# Evaluation_Board.net
KiCad netlist of a schematic drawn in EAGLE
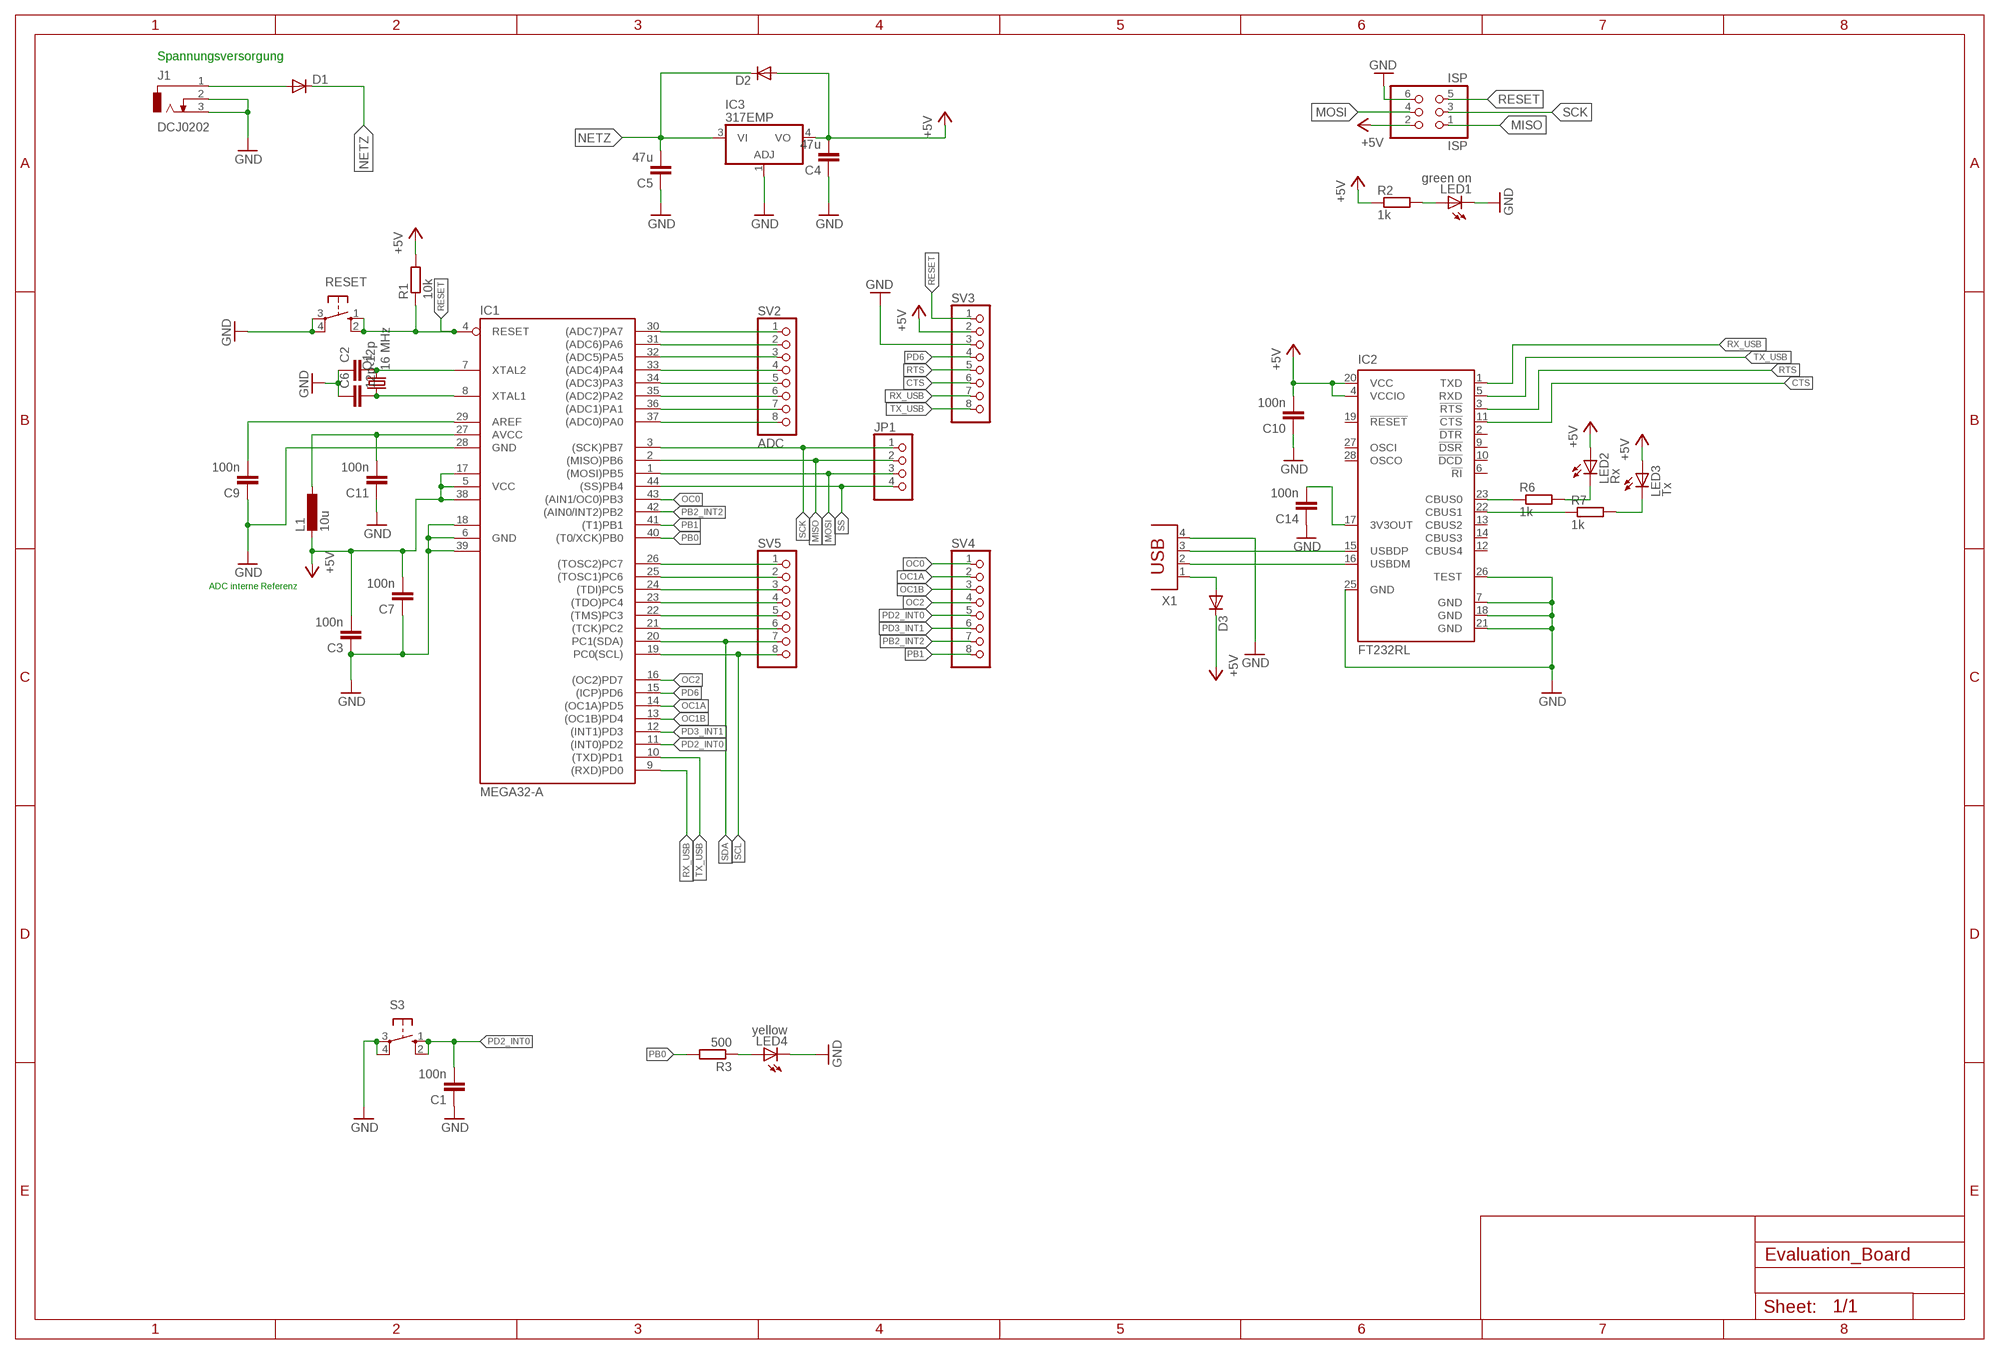
[diagram p0: schematic, sheet 1]

(export (version "E")
  (design (tool "Eeschema 10.0.6"))
  (components
    (comp (ref "C1")
      (value "100n")
      (footprint "eagle-import:C0805")
      (libsource (lib "eagle-import") (part "C-EUC0805"))
    )
    (comp (ref "C2")
      (value "12p")
      (footprint "eagle-import:C0805")
      (libsource (lib "eagle-import") (part "C-EUC0805"))
    )
    (comp (ref "C3")
      (value "100n")
      (footprint "eagle-import:C0805")
      (libsource (lib "eagle-import") (part "C-EUC0805"))
    )
    (comp (ref "C4")
      (value "47u")
      (footprint "eagle-import:C0805")
      (libsource (lib "eagle-import") (part "C-EUC0805"))
    )
    (comp (ref "C5")
      (value "47u")
      (footprint "eagle-import:C0805")
      (libsource (lib "eagle-import") (part "C-EUC0805"))
    )
    (comp (ref "C6")
      (value "12p")
      (footprint "eagle-import:C0805")
      (libsource (lib "eagle-import") (part "C-EUC0805"))
    )
    (comp (ref "C7")
      (value "100n")
      (footprint "eagle-import:C0805")
      (libsource (lib "eagle-import") (part "C-EUC0805"))
    )
    (comp (ref "C9")
      (value "100n")
      (footprint "eagle-import:C0805")
      (libsource (lib "eagle-import") (part "C-EUC0805"))
    )
    (comp (ref "C10")
      (value "100n")
      (footprint "eagle-import:C0805")
      (libsource (lib "eagle-import") (part "C-EUC0805"))
    )
    (comp (ref "C11")
      (value "100n")
      (footprint "eagle-import:C0805")
      (libsource (lib "eagle-import") (part "C-EUC0805"))
    )
    (comp (ref "C14")
      (value "100n")
      (footprint "eagle-import:C0805")
      (libsource (lib "eagle-import") (part "C-EUC0805"))
    )
    (comp (ref "D1")
      (value "DIODE-MINIMELF")
      (footprint "eagle-import:MINIMELF")
      (libsource (lib "eagle-import") (part "DIODE-MINIMELF"))
    )
    (comp (ref "D2")
      (value "DIODE-MINIMELF")
      (footprint "eagle-import:MINIMELF")
      (libsource (lib "eagle-import") (part "DIODE-MINIMELF"))
    )
    (comp (ref "D3")
      (value "DIODE-MINIMELF")
      (footprint "eagle-import:MINIMELF")
      (libsource (lib "eagle-import") (part "DIODE-MINIMELF"))
    )
    (comp (ref "IC1")
      (value "MEGA32-A")
      (footprint "eagle-import:TQFP44")
      (fields (field (name "MPN") "ATMEGA32-16AU"))
      (libsource (lib "eagle-import") (part "MEGA32-A"))
    )
    (comp (ref "IC2")
      (value "FT232RL")
      (footprint "eagle-import:SSOP28")
      (libsource (lib "eagle-import") (part "FT232RL"))
    )
    (comp (ref "IC3")
      (value "317EMP")
      (footprint "eagle-import:SOT223")
      (libsource (lib "eagle-import") (part "317EMP"))
    )
    (comp (ref "ISP")
      (value "ISP")
      (footprint "eagle-import:2X03")
      (libsource (lib "eagle-import") (part "PINHD-2X3"))
    )
    (comp (ref "J1")
      (value "DCJ0202")
      (footprint "eagle-import:DCJ0202")
      (libsource (lib "eagle-import") (part "DCJ0202"))
    )
    (comp (ref "JP1")
      (value "PINHD-1X4")
      (footprint "eagle-import:1X04")
      (libsource (lib "eagle-import") (part "PINHD-1X4"))
    )
    (comp (ref "L1")
      (value "10u")
      (footprint "eagle-import:L3225M")
      (libsource (lib "eagle-import") (part "L-EUL3225M"))
    )
    (comp (ref "LED1")
      (value "green on")
      (footprint "eagle-import:SML0805")
      (libsource (lib "eagle-import") (part "LEDSML0805"))
    )
    (comp (ref "LED2")
      (value "Rx")
      (footprint "eagle-import:SML0805")
      (libsource (lib "eagle-import") (part "LEDSML0805"))
    )
    (comp (ref "LED3")
      (value "Tx")
      (footprint "eagle-import:SML0805")
      (libsource (lib "eagle-import") (part "LEDSML0805"))
    )
    (comp (ref "LED4")
      (value "yellow")
      (footprint "eagle-import:SML0805")
      (libsource (lib "eagle-import") (part "LEDSML0805"))
    )
    (comp (ref "Q1")
      (value "16 MHz")
      (footprint "eagle-import:HC49UP")
      (libsource (lib "eagle-import") (part "CRYSTALHC49UP"))
    )
    (comp (ref "R1")
      (value "10k")
      (footprint "eagle-import:R0805")
      (libsource (lib "eagle-import") (part "R-EU_R0805"))
    )
    (comp (ref "R2")
      (value "1k")
      (footprint "eagle-import:R0805")
      (libsource (lib "eagle-import") (part "R-EU_R0805"))
    )
    (comp (ref "R3")
      (value "500")
      (footprint "eagle-import:R0805")
      (libsource (lib "eagle-import") (part "R-EU_R0805"))
    )
    (comp (ref "R6")
      (value "1k")
      (footprint "eagle-import:R0805")
      (libsource (lib "eagle-import") (part "R-EU_R0805"))
    )
    (comp (ref "R7")
      (value "1k")
      (footprint "eagle-import:R0805")
      (libsource (lib "eagle-import") (part "R-EU_R0805"))
    )
    (comp (ref "RESET")
      (value "10-XX")
      (footprint "eagle-import:B3F-10XX")
      (fields (field (name "MPN") "B3F-1000"))
      (libsource (lib "eagle-import") (part "10-XX"))
    )
    (comp (ref "S3")
      (value "10-XX")
      (footprint "eagle-import:B3F-10XX")
      (fields (field (name "MPN") "B3F-1000"))
      (libsource (lib "eagle-import") (part "10-XX"))
    )
    (comp (ref "SV2")
      (value "ADC")
      (footprint "eagle-import:1X08")
      (libsource (lib "eagle-import") (part "PINHD-1X8"))
    )
    (comp (ref "SV3")
      (value "PINHD-1X8")
      (footprint "eagle-import:1X08")
      (libsource (lib "eagle-import") (part "PINHD-1X8"))
    )
    (comp (ref "SV4")
      (value "PINHD-1X8")
      (footprint "eagle-import:1X08")
      (libsource (lib "eagle-import") (part "PINHD-1X8"))
    )
    (comp (ref "SV5")
      (value "PINHD-1X8")
      (footprint "eagle-import:1X08")
      (libsource (lib "eagle-import") (part "PINHD-1X8"))
    )
    (comp (ref "X1")
      (value "USB-B-BUCHSE-HORIZONTAL")
      (footprint "eagle-import:USB-B-BUCHSE-HORIZONTAL")
      (libsource (lib "eagle-import") (part "USB-B-BUCHSE-HORIZONTAL"))
    )
  )
  (nets
    (net (code "1") (name "+5V") (class "Default")
      (node (ref "C10") (pin "2") (pinfunction "2_2") (pintype "passive"))
      (node (ref "C3") (pin "2") (pinfunction "2_2") (pintype "passive"))
      (node (ref "C4") (pin "2") (pinfunction "2_2") (pintype "passive"))
      (node (ref "C7") (pin "2") (pinfunction "2_2") (pintype "passive"))
      (node (ref "D2") (pin "A") (pinfunction "A_A") (pintype "passive"))
      (node (ref "D3") (pin "C") (pinfunction "C_C") (pintype "passive"))
      (node (ref "IC1") (pin "17") (pinfunction "VCC1_17") (pintype "power_in"))
      (node (ref "IC1") (pin "38") (pinfunction "VCC2_38") (pintype "power_in"))
      (node (ref "IC1") (pin "5") (pinfunction "VCC_5") (pintype "power_in"))
      (node (ref "IC2") (pin "20") (pinfunction "VCC_20") (pintype "power_in"))
      (node (ref "IC2") (pin "4") (pinfunction "VCCIO_4") (pintype "power_in"))
      (node (ref "IC3") (pin "4") (pinfunction "VO_4") (pintype "passive"))
      (node (ref "ISP") (pin "2") (pinfunction "2_2") (pintype "passive"))
      (node (ref "L1") (pin "2") (pinfunction "2_2") (pintype "passive"))
      (node (ref "LED2") (pin "A") (pinfunction "A_A") (pintype "passive"))
      (node (ref "LED3") (pin "A") (pinfunction "A_A") (pintype "passive"))
      (node (ref "R1") (pin "2") (pinfunction "2_2") (pintype "passive"))
      (node (ref "R2") (pin "1") (pinfunction "1_1") (pintype "passive"))
      (node (ref "SV3") (pin "2") (pinfunction "2_2") (pintype "passive"))
    )
    (net (code "2") (name "CTS") (class "Default")
      (node (ref "IC2") (pin "11") (pinfunction "~{CTS}_11") (pintype "input"))
      (node (ref "SV3") (pin "6") (pinfunction "6_6") (pintype "passive"))
    )
    (net (code "3") (name "GND") (class "Default")
      (node (ref "C1") (pin "1") (pinfunction "1_1") (pintype "passive"))
      (node (ref "C10") (pin "1") (pinfunction "1_1") (pintype "passive"))
      (node (ref "C11") (pin "1") (pinfunction "1_1") (pintype "passive"))
      (node (ref "C14") (pin "1") (pinfunction "1_1") (pintype "passive"))
      (node (ref "C2") (pin "1") (pinfunction "1_1") (pintype "passive"))
      (node (ref "C3") (pin "1") (pinfunction "1_1") (pintype "passive"))
      (node (ref "C4") (pin "1") (pinfunction "1_1") (pintype "passive"))
      (node (ref "C5") (pin "1") (pinfunction "1_1") (pintype "passive"))
      (node (ref "C6") (pin "1") (pinfunction "1_1") (pintype "passive"))
      (node (ref "C7") (pin "1") (pinfunction "1_1") (pintype "passive"))
      (node (ref "C9") (pin "1") (pinfunction "1_1") (pintype "passive"))
      (node (ref "IC1") (pin "18") (pinfunction "GND1_18") (pintype "power_in"))
      (node (ref "IC1") (pin "28") (pinfunction "GND_28") (pintype "power_in"))
      (node (ref "IC1") (pin "39") (pinfunction "GND2_39") (pintype "power_in"))
      (node (ref "IC1") (pin "6") (pinfunction "GND_6") (pintype "power_in"))
      (node (ref "IC2") (pin "18") (pinfunction "GND_18") (pintype "power_in"))
      (node (ref "IC2") (pin "21") (pinfunction "GND_21") (pintype "power_in"))
      (node (ref "IC2") (pin "25") (pinfunction "GND_25") (pintype "power_in"))
      (node (ref "IC2") (pin "26") (pinfunction "TEST_26") (pintype "input"))
      (node (ref "IC2") (pin "7") (pinfunction "GND_7") (pintype "power_in"))
      (node (ref "IC3") (pin "1") (pinfunction "ADJ_1") (pintype "input"))
      (node (ref "ISP") (pin "6") (pinfunction "6_6") (pintype "passive"))
      (node (ref "J1") (pin "2") (pinfunction "2_2") (pintype "passive"))
      (node (ref "J1") (pin "3") (pinfunction "3_3") (pintype "passive"))
      (node (ref "LED1") (pin "C") (pinfunction "C_C") (pintype "passive"))
      (node (ref "LED4") (pin "C") (pinfunction "C_C") (pintype "passive"))
      (node (ref "RESET") (pin "3") (pinfunction "P_3") (pintype "passive"))
      (node (ref "RESET") (pin "4") (pinfunction "P1_4") (pintype "passive"))
      (node (ref "S3") (pin "3") (pinfunction "P_3") (pintype "passive"))
      (node (ref "S3") (pin "4") (pinfunction "P1_4") (pintype "passive"))
      (node (ref "SV3") (pin "3") (pinfunction "3_3") (pintype "passive"))
      (node (ref "X1") (pin "4") (pinfunction "4_4") (pintype "passive"))
    )
    (net (code "4") (name "MISO") (class "Default")
      (node (ref "IC1") (pin "2") (pinfunction "(MISO)PB6_2") (pintype "bidirectional"))
      (node (ref "ISP") (pin "1") (pinfunction "1_1") (pintype "passive"))
      (node (ref "JP1") (pin "2") (pinfunction "2_2") (pintype "passive"))
    )
    (net (code "5") (name "MOSI") (class "Default")
      (node (ref "IC1") (pin "1") (pinfunction "(MOSI)PB5_1") (pintype "bidirectional"))
      (node (ref "ISP") (pin "4") (pinfunction "4_4") (pintype "passive"))
      (node (ref "JP1") (pin "3") (pinfunction "3_3") (pintype "passive"))
    )
    (net (code "6") (name "NETZ") (class "Default")
      (node (ref "C5") (pin "2") (pinfunction "2_2") (pintype "passive"))
      (node (ref "D1") (pin "C") (pinfunction "C_C") (pintype "passive"))
      (node (ref "D2") (pin "C") (pinfunction "C_C") (pintype "passive"))
      (node (ref "IC3") (pin "3") (pinfunction "VI_3") (pintype "input"))
    )
    (net (code "7") (name "Net-(D1-PadA)") (class "Default")
      (node (ref "D1") (pin "A") (pinfunction "A_A") (pintype "passive"))
      (node (ref "J1") (pin "1") (pinfunction "1_1") (pintype "passive"))
    )
    (net (code "8") (name "Net-(D3-PadA)") (class "Default")
      (node (ref "D3") (pin "A") (pinfunction "A_A") (pintype "passive"))
      (node (ref "X1") (pin "1") (pinfunction "1_1") (pintype "passive"))
    )
    (net (code "9") (name "Net-(IC1-(ADC0)PA0)") (class "Default")
      (node (ref "IC1") (pin "37") (pinfunction "(ADC0)PA0_37") (pintype "bidirectional"))
      (node (ref "SV2") (pin "8") (pinfunction "8_8") (pintype "passive"))
    )
    (net (code "10") (name "Net-(IC1-(ADC1)PA1)") (class "Default")
      (node (ref "IC1") (pin "36") (pinfunction "(ADC1)PA1_36") (pintype "bidirectional"))
      (node (ref "SV2") (pin "7") (pinfunction "7_7") (pintype "passive"))
    )
    (net (code "11") (name "Net-(IC1-(ADC2)PA2)") (class "Default")
      (node (ref "IC1") (pin "35") (pinfunction "(ADC2)PA2_35") (pintype "bidirectional"))
      (node (ref "SV2") (pin "6") (pinfunction "6_6") (pintype "passive"))
    )
    (net (code "12") (name "Net-(IC1-(ADC3)PA3)") (class "Default")
      (node (ref "IC1") (pin "34") (pinfunction "(ADC3)PA3_34") (pintype "bidirectional"))
      (node (ref "SV2") (pin "5") (pinfunction "5_5") (pintype "passive"))
    )
    (net (code "13") (name "Net-(IC1-(ADC4)PA4)") (class "Default")
      (node (ref "IC1") (pin "33") (pinfunction "(ADC4)PA4_33") (pintype "bidirectional"))
      (node (ref "SV2") (pin "4") (pinfunction "4_4") (pintype "passive"))
    )
    (net (code "14") (name "Net-(IC1-(ADC5)PA5)") (class "Default")
      (node (ref "IC1") (pin "32") (pinfunction "(ADC5)PA5_32") (pintype "bidirectional"))
      (node (ref "SV2") (pin "3") (pinfunction "3_3") (pintype "passive"))
    )
    (net (code "15") (name "Net-(IC1-(ADC6)PA6)") (class "Default")
      (node (ref "IC1") (pin "31") (pinfunction "(ADC6)PA6_31") (pintype "bidirectional"))
      (node (ref "SV2") (pin "2") (pinfunction "2_2") (pintype "passive"))
    )
    (net (code "16") (name "Net-(IC1-(ADC7)PA7)") (class "Default")
      (node (ref "IC1") (pin "30") (pinfunction "(ADC7)PA7_30") (pintype "bidirectional"))
      (node (ref "SV2") (pin "1") (pinfunction "1_1") (pintype "passive"))
    )
    (net (code "17") (name "Net-(IC1-(TCK)PC2)") (class "Default")
      (node (ref "IC1") (pin "21") (pinfunction "(TCK)PC2_21") (pintype "bidirectional"))
      (node (ref "SV5") (pin "6") (pinfunction "6_6") (pintype "passive"))
    )
    (net (code "18") (name "Net-(IC1-(TDI)PC5)") (class "Default")
      (node (ref "IC1") (pin "24") (pinfunction "(TDI)PC5_24") (pintype "bidirectional"))
      (node (ref "SV5") (pin "3") (pinfunction "3_3") (pintype "passive"))
    )
    (net (code "19") (name "Net-(IC1-(TDO)PC4)") (class "Default")
      (node (ref "IC1") (pin "23") (pinfunction "(TDO)PC4_23") (pintype "bidirectional"))
      (node (ref "SV5") (pin "4") (pinfunction "4_4") (pintype "passive"))
    )
    (net (code "20") (name "Net-(IC1-(TMS)PC3)") (class "Default")
      (node (ref "IC1") (pin "22") (pinfunction "(TMS)PC3_22") (pintype "bidirectional"))
      (node (ref "SV5") (pin "5") (pinfunction "5_5") (pintype "passive"))
    )
    (net (code "21") (name "Net-(IC1-(TOSC1)PC6)") (class "Default")
      (node (ref "IC1") (pin "25") (pinfunction "(TOSC1)PC6_25") (pintype "bidirectional"))
      (node (ref "SV5") (pin "2") (pinfunction "2_2") (pintype "passive"))
    )
    (net (code "22") (name "Net-(IC1-(TOSC2)PC7)") (class "Default")
      (node (ref "IC1") (pin "26") (pinfunction "(TOSC2)PC7_26") (pintype "bidirectional"))
      (node (ref "SV5") (pin "1") (pinfunction "1_1") (pintype "passive"))
    )
    (net (code "23") (name "Net-(IC1-AREF)") (class "Default")
      (node (ref "C9") (pin "2") (pinfunction "2_2") (pintype "passive"))
      (node (ref "IC1") (pin "29") (pinfunction "AREF_29") (pintype "passive"))
    )
    (net (code "24") (name "Net-(IC1-AVCC)") (class "Default")
      (node (ref "C11") (pin "2") (pinfunction "2_2") (pintype "passive"))
      (node (ref "IC1") (pin "27") (pinfunction "AVCC_27") (pintype "power_in"))
      (node (ref "L1") (pin "1") (pinfunction "1_1") (pintype "passive"))
    )
    (net (code "25") (name "Net-(IC1-XTAL1)") (class "Default")
      (node (ref "C6") (pin "2") (pinfunction "2_2") (pintype "passive"))
      (node (ref "IC1") (pin "8") (pinfunction "XTAL1_8") (pintype "bidirectional"))
      (node (ref "Q1") (pin "1") (pinfunction "1_1") (pintype "passive"))
    )
    (net (code "26") (name "Net-(IC1-XTAL2)") (class "Default")
      (node (ref "C2") (pin "2") (pinfunction "2_2") (pintype "passive"))
      (node (ref "IC1") (pin "7") (pinfunction "XTAL2_7") (pintype "bidirectional"))
      (node (ref "Q1") (pin "2") (pinfunction "2_2") (pintype "passive"))
    )
    (net (code "27") (name "Net-(IC2-3V3OUT)") (class "Default")
      (node (ref "C14") (pin "2") (pinfunction "2_2") (pintype "passive"))
      (node (ref "IC2") (pin "17") (pinfunction "3V3OUT_17") (pintype "output"))
    )
    (net (code "28") (name "Net-(IC2-CBUS0)") (class "Default")
      (node (ref "IC2") (pin "23") (pinfunction "CBUS0_23") (pintype "bidirectional"))
      (node (ref "R6") (pin "1") (pinfunction "1_1") (pintype "passive"))
    )
    (net (code "29") (name "Net-(IC2-CBUS1)") (class "Default")
      (node (ref "IC2") (pin "22") (pinfunction "CBUS1_22") (pintype "bidirectional"))
      (node (ref "R7") (pin "1") (pinfunction "1_1") (pintype "passive"))
    )
    (net (code "30") (name "Net-(IC2-USBDM)") (class "Default")
      (node (ref "IC2") (pin "16") (pinfunction "USBDM_16") (pintype "bidirectional"))
      (node (ref "X1") (pin "2") (pinfunction "2_2") (pintype "passive"))
    )
    (net (code "31") (name "Net-(IC2-USBDP)") (class "Default")
      (node (ref "IC2") (pin "15") (pinfunction "USBDP_15") (pintype "bidirectional"))
      (node (ref "X1") (pin "3") (pinfunction "3_3") (pintype "passive"))
    )
    (net (code "32") (name "Net-(LED1-PadA)") (class "Default")
      (node (ref "LED1") (pin "A") (pinfunction "A_A") (pintype "passive"))
      (node (ref "R2") (pin "2") (pinfunction "2_2") (pintype "passive"))
    )
    (net (code "33") (name "Net-(LED2-PadC)") (class "Default")
      (node (ref "LED2") (pin "C") (pinfunction "C_C") (pintype "passive"))
      (node (ref "R6") (pin "2") (pinfunction "2_2") (pintype "passive"))
    )
    (net (code "34") (name "Net-(LED3-PadC)") (class "Default")
      (node (ref "LED3") (pin "C") (pinfunction "C_C") (pintype "passive"))
      (node (ref "R7") (pin "2") (pinfunction "2_2") (pintype "passive"))
    )
    (net (code "35") (name "Net-(LED4-PadA)") (class "Default")
      (node (ref "LED4") (pin "A") (pinfunction "A_A") (pintype "passive"))
      (node (ref "R3") (pin "1") (pinfunction "1_1") (pintype "passive"))
    )
    (net (code "36") (name "OC0") (class "Default")
      (node (ref "IC1") (pin "43") (pinfunction "(AIN1/OC0)PB3_43") (pintype "bidirectional"))
      (node (ref "SV4") (pin "1") (pinfunction "1_1") (pintype "passive"))
    )
    (net (code "37") (name "OC1A") (class "Default")
      (node (ref "IC1") (pin "14") (pinfunction "(OC1A)PD5_14") (pintype "bidirectional"))
      (node (ref "SV4") (pin "2") (pinfunction "2_2") (pintype "passive"))
    )
    (net (code "38") (name "OC1B") (class "Default")
      (node (ref "IC1") (pin "13") (pinfunction "(OC1B)PD4_13") (pintype "bidirectional"))
      (node (ref "SV4") (pin "3") (pinfunction "3_3") (pintype "passive"))
    )
    (net (code "39") (name "OC2") (class "Default")
      (node (ref "IC1") (pin "16") (pinfunction "(OC2)PD7_16") (pintype "bidirectional"))
      (node (ref "SV4") (pin "4") (pinfunction "4_4") (pintype "passive"))
    )
    (net (code "40") (name "PB0") (class "Default")
      (node (ref "IC1") (pin "40") (pinfunction "(T0/XCK)PB0_40") (pintype "bidirectional"))
      (node (ref "R3") (pin "2") (pinfunction "2_2") (pintype "passive"))
    )
    (net (code "41") (name "PB1") (class "Default")
      (node (ref "IC1") (pin "41") (pinfunction "(T1)PB1_41") (pintype "bidirectional"))
      (node (ref "SV4") (pin "8") (pinfunction "8_8") (pintype "passive"))
    )
    (net (code "42") (name "PB2_INT2") (class "Default")
      (node (ref "IC1") (pin "42") (pinfunction "(AIN0/INT2)PB2_42") (pintype "bidirectional"))
      (node (ref "SV4") (pin "7") (pinfunction "7_7") (pintype "passive"))
    )
    (net (code "43") (name "PD2_INT0") (class "Default")
      (node (ref "C1") (pin "2") (pinfunction "2_2") (pintype "passive"))
      (node (ref "IC1") (pin "11") (pinfunction "(INT0)PD2_11") (pintype "bidirectional"))
      (node (ref "S3") (pin "1") (pinfunction "S_1") (pintype "passive"))
      (node (ref "S3") (pin "2") (pinfunction "S1_2") (pintype "passive"))
      (node (ref "SV4") (pin "5") (pinfunction "5_5") (pintype "passive"))
    )
    (net (code "44") (name "PD3_INT1") (class "Default")
      (node (ref "IC1") (pin "12") (pinfunction "(INT1)PD3_12") (pintype "bidirectional"))
      (node (ref "SV4") (pin "6") (pinfunction "6_6") (pintype "passive"))
    )
    (net (code "45") (name "PD6") (class "Default")
      (node (ref "IC1") (pin "15") (pinfunction "(ICP)PD6_15") (pintype "bidirectional"))
      (node (ref "SV3") (pin "4") (pinfunction "4_4") (pintype "passive"))
    )
    (net (code "46") (name "RESET") (class "Default")
      (node (ref "IC1") (pin "4") (pinfunction "RESET_4") (pintype "input"))
      (node (ref "ISP") (pin "5") (pinfunction "5_5") (pintype "passive"))
      (node (ref "R1") (pin "1") (pinfunction "1_1") (pintype "passive"))
      (node (ref "RESET") (pin "1") (pinfunction "S_1") (pintype "passive"))
      (node (ref "RESET") (pin "2") (pinfunction "S1_2") (pintype "passive"))
      (node (ref "SV3") (pin "1") (pinfunction "1_1") (pintype "passive"))
    )
    (net (code "47") (name "RTS") (class "Default")
      (node (ref "IC2") (pin "3") (pinfunction "~{RTS}_3") (pintype "output"))
      (node (ref "SV3") (pin "5") (pinfunction "5_5") (pintype "passive"))
    )
    (net (code "48") (name "RX_USB") (class "Default")
      (node (ref "IC1") (pin "9") (pinfunction "(RXD)PD0_9") (pintype "bidirectional"))
      (node (ref "IC2") (pin "1") (pinfunction "TXD_1") (pintype "output"))
      (node (ref "SV3") (pin "7") (pinfunction "7_7") (pintype "passive"))
    )
    (net (code "49") (name "SCK") (class "Default")
      (node (ref "IC1") (pin "3") (pinfunction "(SCK)PB7_3") (pintype "bidirectional"))
      (node (ref "ISP") (pin "3") (pinfunction "3_3") (pintype "passive"))
      (node (ref "JP1") (pin "1") (pinfunction "1_1") (pintype "passive"))
    )
    (net (code "50") (name "SCL") (class "Default")
      (node (ref "IC1") (pin "19") (pinfunction "PC0(SCL)_19") (pintype "bidirectional"))
      (node (ref "SV5") (pin "8") (pinfunction "8_8") (pintype "passive"))
    )
    (net (code "51") (name "SDA") (class "Default")
      (node (ref "IC1") (pin "20") (pinfunction "PC1(SDA)_20") (pintype "bidirectional"))
      (node (ref "SV5") (pin "7") (pinfunction "7_7") (pintype "passive"))
    )
    (net (code "52") (name "SS") (class "Default")
      (node (ref "IC1") (pin "44") (pinfunction "(SS)PB4_44") (pintype "bidirectional"))
      (node (ref "JP1") (pin "4") (pinfunction "4_4") (pintype "passive"))
    )
    (net (code "53") (name "TX_USB") (class "Default")
      (node (ref "IC1") (pin "10") (pinfunction "(TXD)PD1_10") (pintype "bidirectional"))
      (node (ref "IC2") (pin "5") (pinfunction "RXD_5") (pintype "input"))
      (node (ref "SV3") (pin "8") (pinfunction "8_8") (pintype "passive"))
    )
    (net (code "54") (name "unconnected-(IC2-CBUS2-Pad13)") (class "Default")
      (node (ref "IC2") (pin "13") (pinfunction "CBUS2_13") (pintype "bidirectional"))
    )
    (net (code "55") (name "unconnected-(IC2-CBUS3-Pad14)") (class "Default")
      (node (ref "IC2") (pin "14") (pinfunction "CBUS3_14") (pintype "bidirectional"))
    )
    (net (code "56") (name "unconnected-(IC2-CBUS4-Pad12)") (class "Default")
      (node (ref "IC2") (pin "12") (pinfunction "CBUS4_12") (pintype "bidirectional"))
    )
    (net (code "57") (name "unconnected-(IC2-OSCI-Pad27)") (class "Default")
      (node (ref "IC2") (pin "27") (pinfunction "OSCI_27") (pintype "input"))
    )
    (net (code "58") (name "unconnected-(IC2-OSCO-Pad28)") (class "Default")
      (node (ref "IC2") (pin "28") (pinfunction "OSCO_28") (pintype "output"))
    )
    (net (code "59") (name "unconnected-(IC2-~{DCD}-Pad10)") (class "Default")
      (node (ref "IC2") (pin "10") (pinfunction "~{DCD}_10") (pintype "input"))
    )
    (net (code "60") (name "unconnected-(IC2-~{DSR}-Pad9)") (class "Default")
      (node (ref "IC2") (pin "9") (pinfunction "~{DSR}_9") (pintype "input"))
    )
    (net (code "61") (name "unconnected-(IC2-~{DTR}-Pad2)") (class "Default")
      (node (ref "IC2") (pin "2") (pinfunction "~{DTR}_2") (pintype "output"))
    )
    (net (code "62") (name "unconnected-(IC2-~{RESET}-Pad19)") (class "Default")
      (node (ref "IC2") (pin "19") (pinfunction "~{RESET}_19") (pintype "input"))
    )
    (net (code "63") (name "unconnected-(IC2-~{RI}-Pad6)") (class "Default")
      (node (ref "IC2") (pin "6") (pinfunction "~{RI}_6") (pintype "input"))
    )
  )
)
